# SCH_create_2023-03-12.net
KiCad netlist of a schematic drawn in EasyEDA
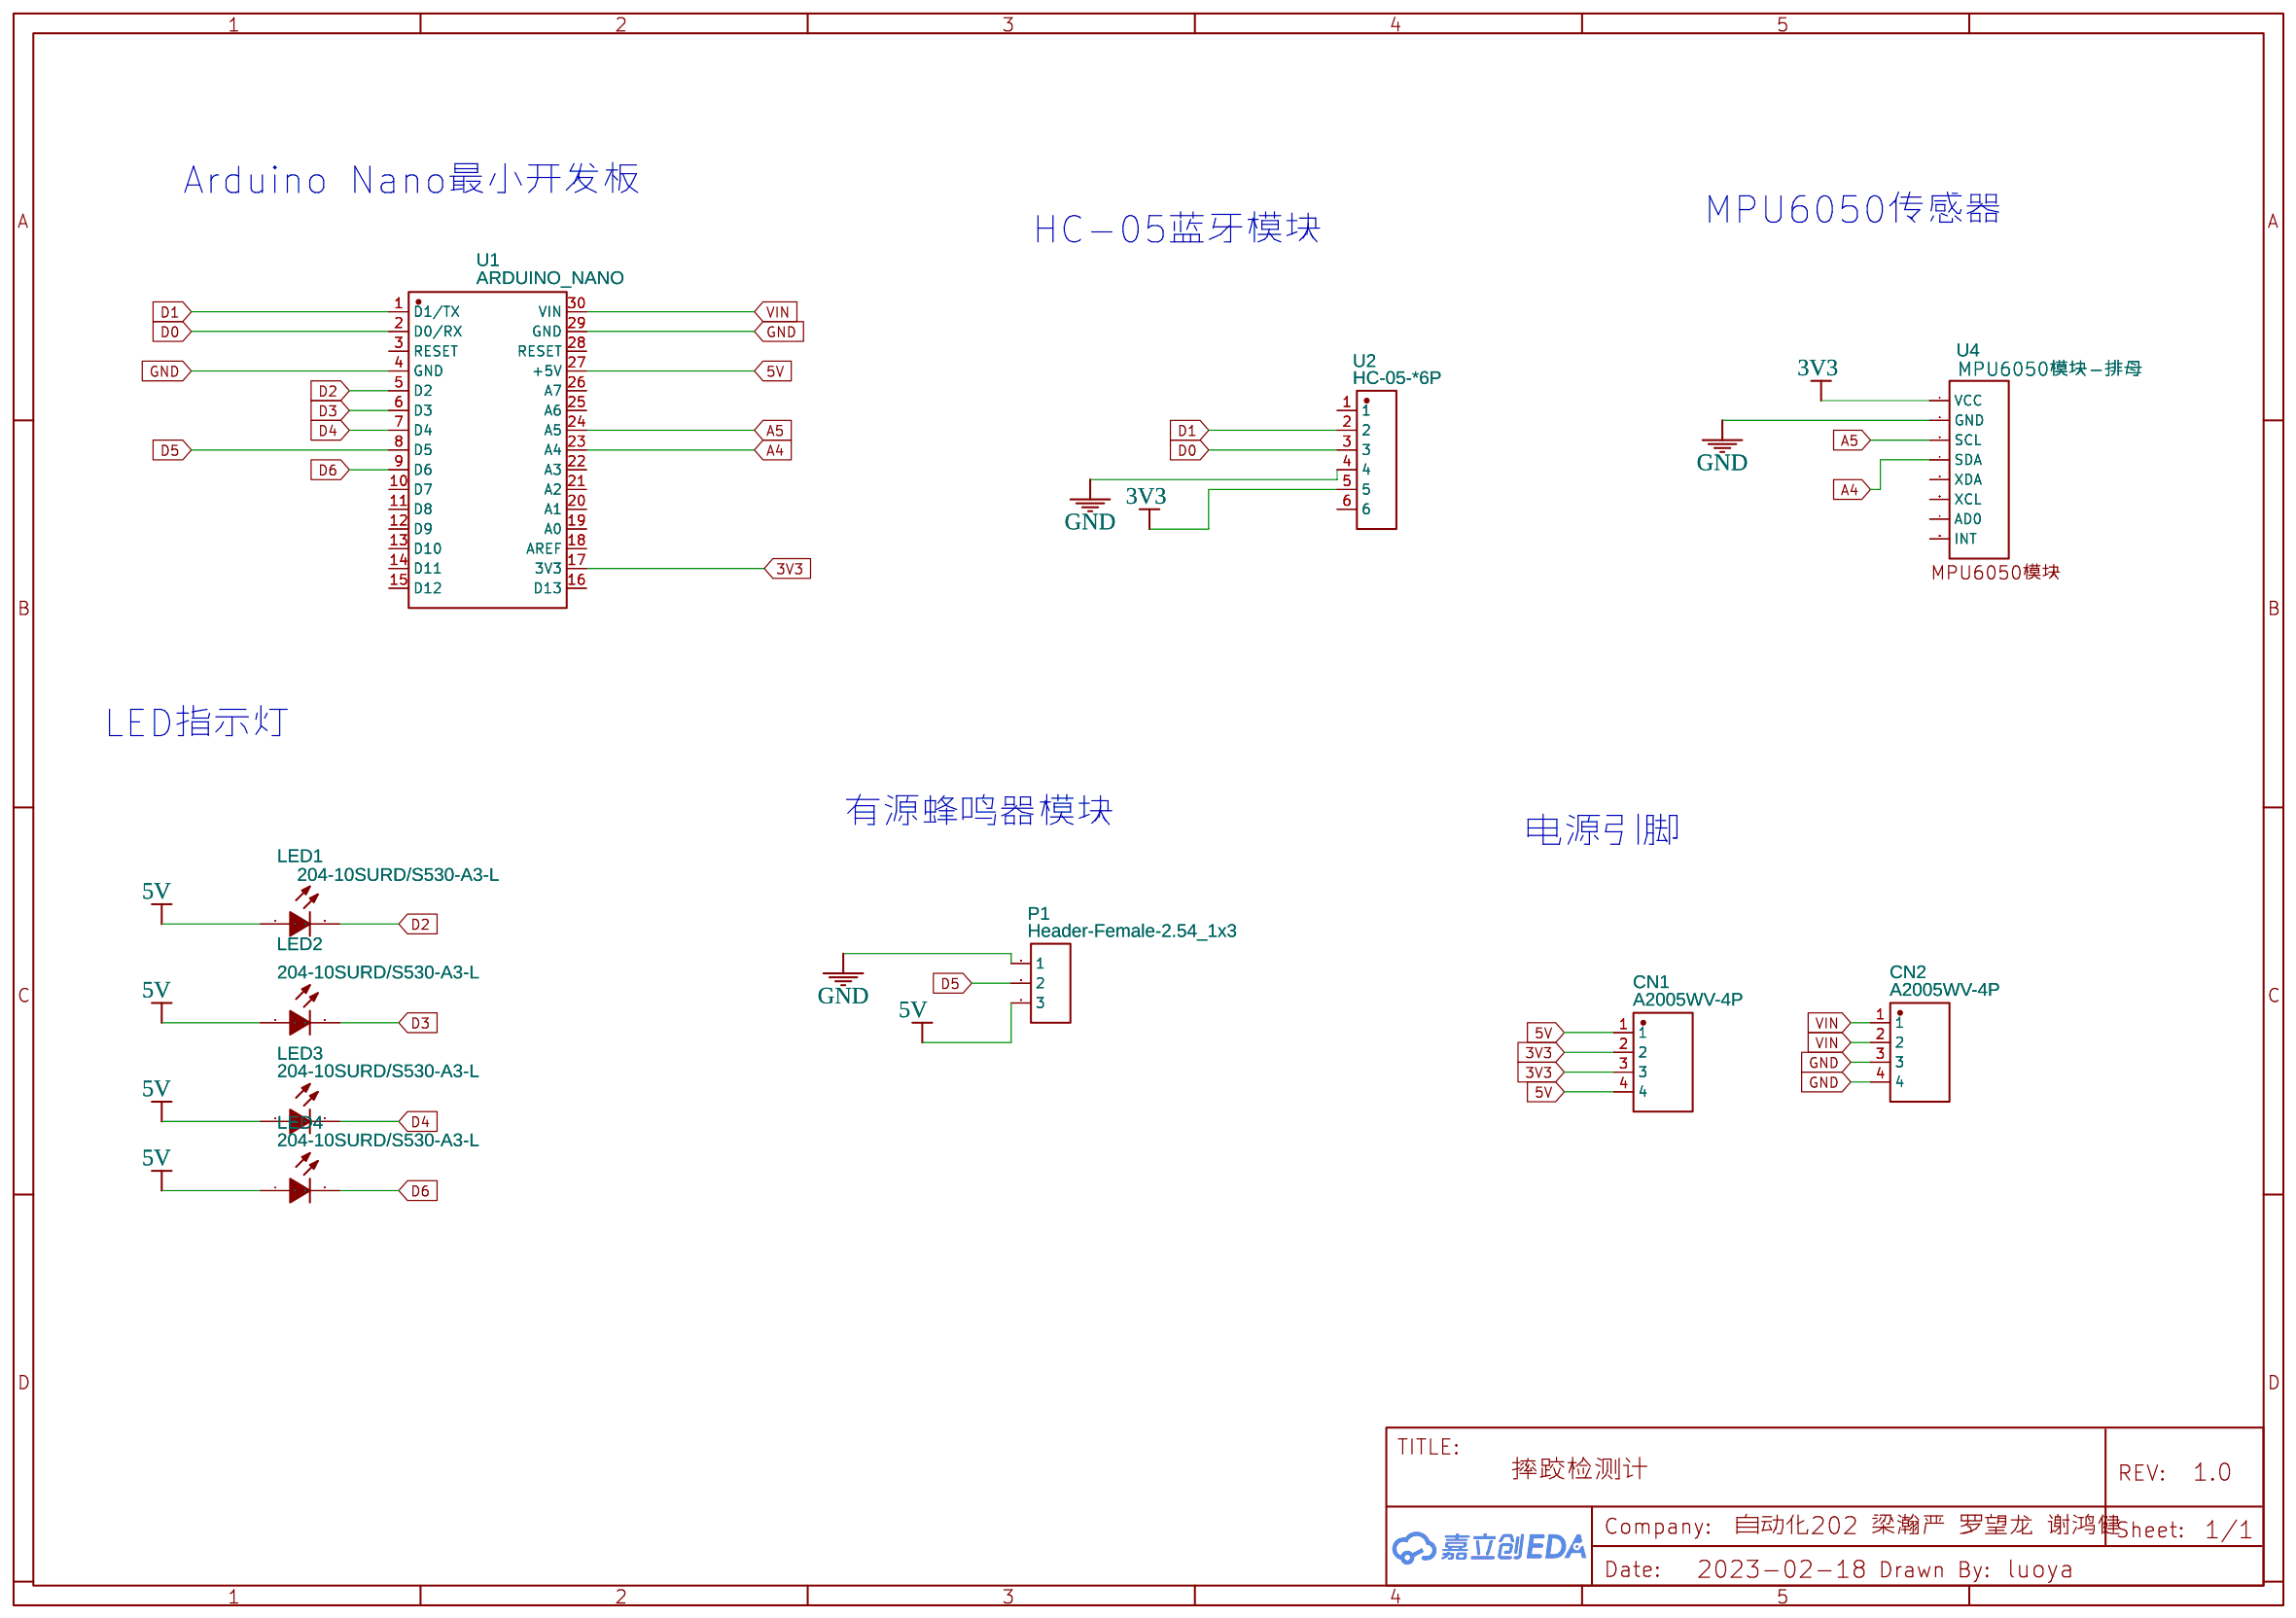
[diagram p0: schematic sheet]

(export (version "E")
  (design (tool "Eeschema 10.0.6"))
  (components
    (comp (ref "CN1")
      (value "A2005WV-4P")
      (fields (field (name "BOM_Supplier Part") "C225256"))
      (libsource (lib "") (part "A2005WV-4P"))
    )
    (comp (ref "CN2")
      (value "A2005WV-4P")
      (fields (field (name "BOM_Supplier Part") "C225256"))
      (libsource (lib "") (part "A2005WV-4P"))
    )
    (comp (ref "LED1")
      (value "204-10SURD/S530-A3-L")
      (fields (field (name "BOM_Supplier Part") "C99771"))
      (libsource (lib "") (part "204-10SURD/S530-A3-L"))
    )
    (comp (ref "LED2")
      (value "204-10SURD/S530-A3-L")
      (fields (field (name "BOM_Supplier Part") "C99771"))
      (libsource (lib "") (part "204-10SURD/S530-A3-L"))
    )
    (comp (ref "LED3")
      (value "204-10SURD/S530-A3-L")
      (fields (field (name "BOM_Supplier Part") "C99771"))
      (libsource (lib "") (part "204-10SURD/S530-A3-L"))
    )
    (comp (ref "LED4")
      (value "204-10SURD/S530-A3-L")
      (fields (field (name "BOM_Supplier Part") "C99771"))
      (libsource (lib "") (part "204-10SURD/S530-A3-L"))
    )
    (comp (ref "P1")
      (value "Header-Female-2.54_1x3")
      (fields
        (field (name "BOM_Manufacturer Part") "2.54-1*3P母")
        (field (name "BOM_Supplier Part") "C146243")
      )
      (libsource (lib "") (part "Header-Female-2.54_1x3"))
    )
    (comp (ref "U1")
      (value "ARDUINO_NANO")
      (fields (field (name "BOM_Supplier Part") "C9900017879"))
      (libsource (lib "") (part "ARDUINO_NANO"))
    )
    (comp (ref "U2")
      (value "HC-05-*6P")
      (fields
        (field (name "BOM_Manufacturer Part") "HC-05_排母*6P")
        (field (name "BOM_Supplier Part") "C9900003093")
      )
      (libsource (lib "") (part "HC-05-*6P"))
    )
    (comp (ref "U4") (value "MPU6050模块-排母") (libsource (lib "") (part "MPU6050模块-排母")))
  )
  (nets
    (net (code "1") (name "3V3") (class "Default")
      (node (ref "CN1") (pin "2") (pinfunction "2_2") (pintype "unspecified"))
      (node (ref "CN1") (pin "3") (pinfunction "3_3") (pintype "unspecified"))
      (node (ref "U1") (pin "17") (pinfunction "3V3_17") (pintype "unspecified"))
      (node (ref "U2") (pin "5") (pinfunction "5_5") (pintype "unspecified"))
      (node (ref "U4") (pin "1") (pinfunction "VCC_1") (pintype "input"))
    )
    (net (code "2") (name "5V") (class "Default")
      (node (ref "CN1") (pin "1") (pinfunction "1_1") (pintype "unspecified"))
      (node (ref "CN1") (pin "4") (pinfunction "4_4") (pintype "unspecified"))
      (node (ref "LED1") (pin "1") (pinfunction "A_1") (pintype "input"))
      (node (ref "LED2") (pin "1") (pinfunction "A_1") (pintype "input"))
      (node (ref "LED3") (pin "1") (pinfunction "A_1") (pintype "input"))
      (node (ref "LED4") (pin "1") (pinfunction "A_1") (pintype "input"))
      (node (ref "P1") (pin "3") (pinfunction "3_3") (pintype "input"))
      (node (ref "U1") (pin "27") (pinfunction "+5V_27") (pintype "unspecified"))
    )
    (net (code "3") (name "A4") (class "Default")
      (node (ref "U1") (pin "23") (pinfunction "A4_23") (pintype "unspecified"))
      (node (ref "U4") (pin "4") (pinfunction "SDA_4") (pintype "input"))
    )
    (net (code "4") (name "A5") (class "Default")
      (node (ref "U1") (pin "24") (pinfunction "A5_24") (pintype "unspecified"))
      (node (ref "U4") (pin "3") (pinfunction "SCL_3") (pintype "input"))
    )
    (net (code "5") (name "D0") (class "Default")
      (node (ref "U1") (pin "2") (pinfunction "D0/RX_2") (pintype "unspecified"))
      (node (ref "U2") (pin "3") (pinfunction "3_3") (pintype "unspecified"))
    )
    (net (code "6") (name "D1") (class "Default")
      (node (ref "U1") (pin "1") (pinfunction "D1/TX_1") (pintype "unspecified"))
      (node (ref "U2") (pin "2") (pinfunction "2_2") (pintype "unspecified"))
    )
    (net (code "7") (name "D2") (class "Default")
      (node (ref "LED1") (pin "2") (pinfunction "K_2") (pintype "input"))
      (node (ref "U1") (pin "5") (pinfunction "D2_5") (pintype "unspecified"))
    )
    (net (code "8") (name "D3") (class "Default")
      (node (ref "LED2") (pin "2") (pinfunction "K_2") (pintype "input"))
      (node (ref "U1") (pin "6") (pinfunction "D3_6") (pintype "unspecified"))
    )
    (net (code "9") (name "D4") (class "Default")
      (node (ref "LED3") (pin "2") (pinfunction "K_2") (pintype "input"))
      (node (ref "U1") (pin "7") (pinfunction "D4_7") (pintype "unspecified"))
    )
    (net (code "10") (name "D5") (class "Default")
      (node (ref "P1") (pin "2") (pinfunction "2_2") (pintype "input"))
      (node (ref "U1") (pin "8") (pinfunction "D5_8") (pintype "unspecified"))
    )
    (net (code "11") (name "D6") (class "Default")
      (node (ref "LED4") (pin "2") (pinfunction "K_2") (pintype "input"))
      (node (ref "U1") (pin "9") (pinfunction "D6_9") (pintype "unspecified"))
    )
    (net (code "12") (name "GND") (class "Default")
      (node (ref "CN2") (pin "3") (pinfunction "3_3") (pintype "unspecified"))
      (node (ref "CN2") (pin "4") (pinfunction "4_4") (pintype "unspecified"))
      (node (ref "P1") (pin "1") (pinfunction "1_1") (pintype "input"))
      (node (ref "U1") (pin "29") (pinfunction "GND_29") (pintype "unspecified"))
      (node (ref "U1") (pin "4") (pinfunction "GND_4") (pintype "unspecified"))
      (node (ref "U2") (pin "4") (pinfunction "4_4") (pintype "unspecified"))
      (node (ref "U4") (pin "2") (pinfunction "GND_2") (pintype "input"))
    )
    (net (code "13") (name "VIN") (class "Default")
      (node (ref "CN2") (pin "1") (pinfunction "1_1") (pintype "unspecified"))
      (node (ref "CN2") (pin "2") (pinfunction "2_2") (pintype "unspecified"))
      (node (ref "U1") (pin "30") (pinfunction "VIN_30") (pintype "unspecified"))
    )
    (net (code "14") (name "unconnected-(U1-A0-Pad19)") (class "Default")
      (node (ref "U1") (pin "19") (pinfunction "A0_19") (pintype "unspecified"))
    )
    (net (code "15") (name "unconnected-(U1-A1-Pad20)") (class "Default")
      (node (ref "U1") (pin "20") (pinfunction "A1_20") (pintype "unspecified"))
    )
    (net (code "16") (name "unconnected-(U1-A2-Pad21)") (class "Default")
      (node (ref "U1") (pin "21") (pinfunction "A2_21") (pintype "unspecified"))
    )
    (net (code "17") (name "unconnected-(U1-A3-Pad22)") (class "Default")
      (node (ref "U1") (pin "22") (pinfunction "A3_22") (pintype "unspecified"))
    )
    (net (code "18") (name "unconnected-(U1-A6-Pad25)") (class "Default")
      (node (ref "U1") (pin "25") (pinfunction "A6_25") (pintype "unspecified"))
    )
    (net (code "19") (name "unconnected-(U1-A7-Pad26)") (class "Default")
      (node (ref "U1") (pin "26") (pinfunction "A7_26") (pintype "unspecified"))
    )
    (net (code "20") (name "unconnected-(U1-AREF-Pad18)") (class "Default")
      (node (ref "U1") (pin "18") (pinfunction "AREF_18") (pintype "unspecified"))
    )
    (net (code "21") (name "unconnected-(U1-D7-Pad10)") (class "Default")
      (node (ref "U1") (pin "10") (pinfunction "D7_10") (pintype "unspecified"))
    )
    (net (code "22") (name "unconnected-(U1-D8-Pad11)") (class "Default")
      (node (ref "U1") (pin "11") (pinfunction "D8_11") (pintype "unspecified"))
    )
    (net (code "23") (name "unconnected-(U1-D9-Pad12)") (class "Default")
      (node (ref "U1") (pin "12") (pinfunction "D9_12") (pintype "unspecified"))
    )
    (net (code "24") (name "unconnected-(U1-D10-Pad13)") (class "Default")
      (node (ref "U1") (pin "13") (pinfunction "D10_13") (pintype "unspecified"))
    )
    (net (code "25") (name "unconnected-(U1-D11-Pad14)") (class "Default")
      (node (ref "U1") (pin "14") (pinfunction "D11_14") (pintype "unspecified"))
    )
    (net (code "26") (name "unconnected-(U1-D12-Pad15)") (class "Default")
      (node (ref "U1") (pin "15") (pinfunction "D12_15") (pintype "unspecified"))
    )
    (net (code "27") (name "unconnected-(U1-D13-Pad16)") (class "Default")
      (node (ref "U1") (pin "16") (pinfunction "D13_16") (pintype "unspecified"))
    )
    (net (code "28") (name "unconnected-(U1-RESET-Pad3)") (class "Default")
      (node (ref "U1") (pin "3") (pinfunction "RESET_3") (pintype "unspecified"))
    )
    (net (code "29") (name "unconnected-(U1-RESET-Pad28)") (class "Default")
      (node (ref "U1") (pin "28") (pinfunction "RESET_28") (pintype "unspecified"))
    )
    (net (code "30") (name "unconnected-(U2-Pad1)") (class "Default")
      (node (ref "U2") (pin "1") (pinfunction "1_1") (pintype "unspecified"))
    )
    (net (code "31") (name "unconnected-(U2-Pad6)") (class "Default")
      (node (ref "U2") (pin "6") (pinfunction "6_6") (pintype "unspecified"))
    )
    (net (code "32") (name "unconnected-(U4-AD0-Pad7)") (class "Default")
      (node (ref "U4") (pin "7") (pinfunction "AD0_7") (pintype "input"))
    )
    (net (code "33") (name "unconnected-(U4-INT-Pad8)") (class "Default")
      (node (ref "U4") (pin "8") (pinfunction "INT_8") (pintype "input"))
    )
    (net (code "34") (name "unconnected-(U4-XCL-Pad6)") (class "Default")
      (node (ref "U4") (pin "6") (pinfunction "XCL_6") (pintype "input"))
    )
    (net (code "35") (name "unconnected-(U4-XDA-Pad5)") (class "Default")
      (node (ref "U4") (pin "5") (pinfunction "XDA_5") (pintype "input"))
    )
  )
)
